# Pg2-Filter_and_Gain.net
KiCad netlist of a schematic drawn in Altium Designer
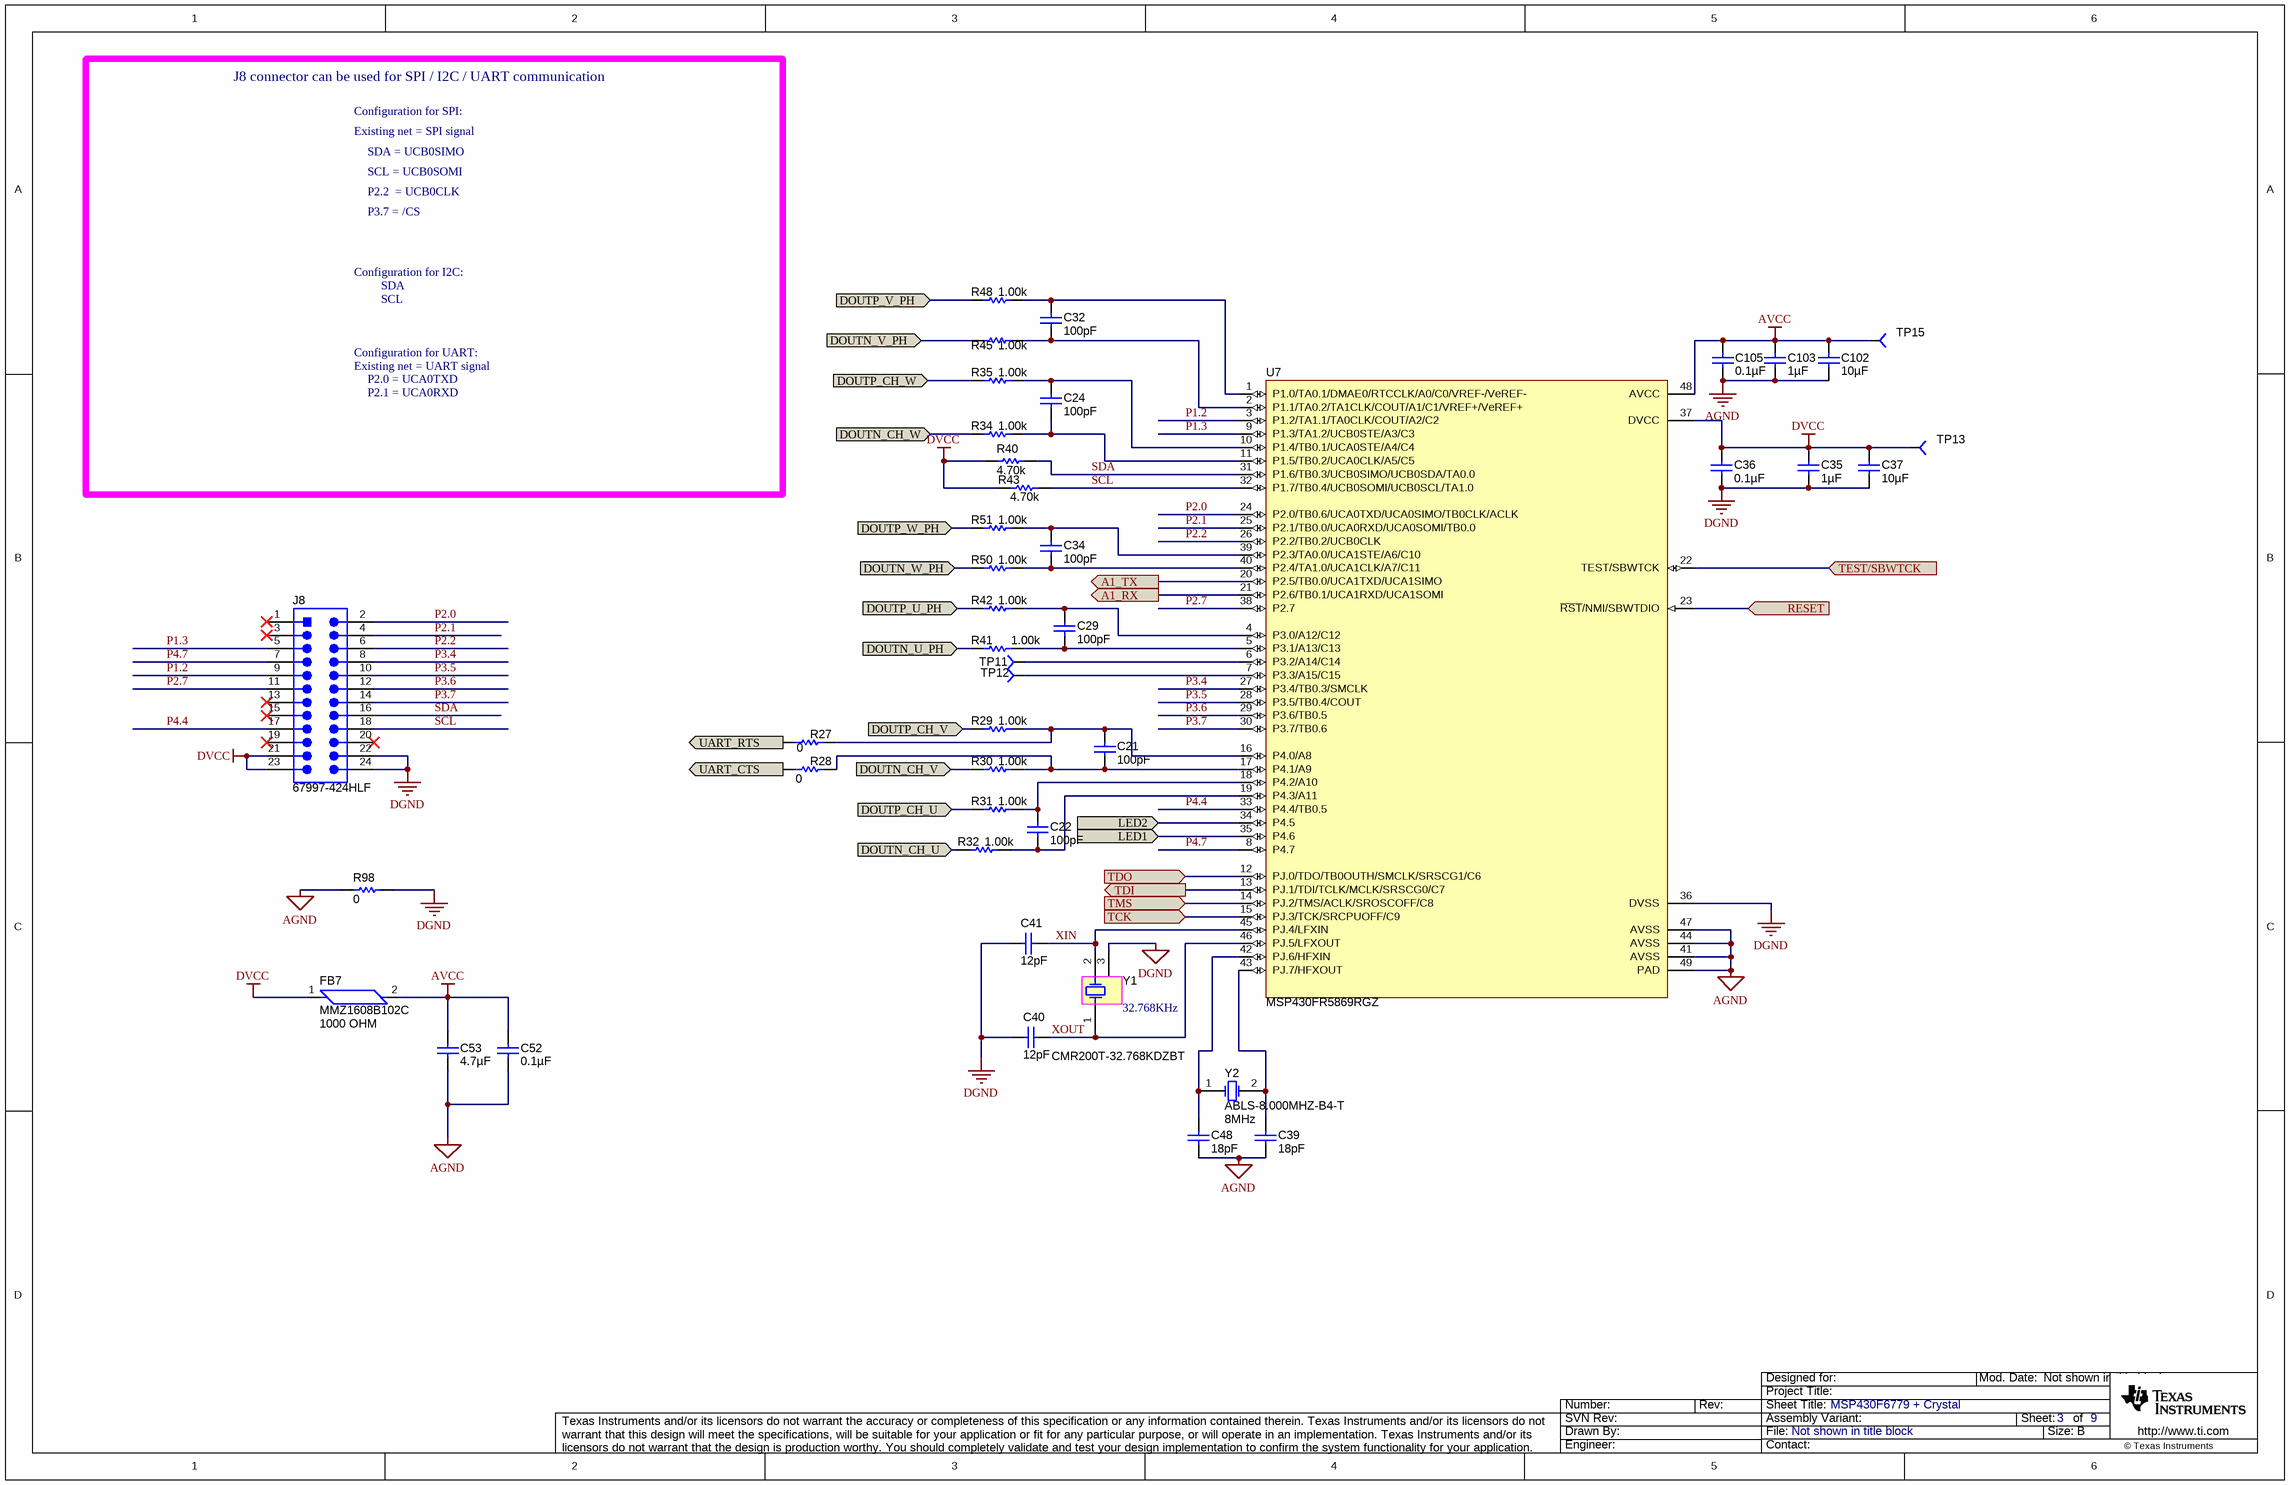
[diagram p0: Pg2-Filter and Gain.SchDoc]

(export (version "E")
  (design (tool "Eeschema 10.0.6"))
  (components
    (comp (ref "C21")
      (value "C0603C101J5GAC")
      (footprint "0603")
      (description "CAP, CERM, 100 pF, 50 V, +/- 5%, C0G/NP0, 0603")
      (fields
        (field (name "VALUEDISPLAYED") "100pF")
        (field (name "MANUFACTURER") "Kemet")
        (field (name "PUBLISHER") "Texas Instruments")
      )
      (libsource (lib "Capacitor_Ceramic") (part "C0603C101J5GAC"))
    )
    (comp (ref "C22")
      (value "C0603C101J5GAC")
      (footprint "0603")
      (description "CAP, CERM, 100 pF, 50 V, +/- 5%, C0G/NP0, 0603")
      (fields
        (field (name "VALUEDISPLAYED") "100pF")
        (field (name "MANUFACTURER") "Kemet")
        (field (name "PUBLISHER") "Texas Instruments")
      )
      (libsource (lib "Capacitor_Ceramic") (part "C0603C101J5GAC"))
    )
    (comp (ref "C24")
      (value "C0603C101J5GAC")
      (footprint "0603")
      (description "CAP, CERM, 100 pF, 50 V, +/- 5%, C0G/NP0, 0603")
      (fields
        (field (name "VALUEDISPLAYED") "100pF")
        (field (name "MANUFACTURER") "Kemet")
        (field (name "PUBLISHER") "Texas Instruments")
      )
      (libsource (lib "Capacitor_Ceramic") (part "C0603C101J5GAC"))
    )
    (comp (ref "C29")
      (value "C0603C101J5GAC")
      (footprint "0603")
      (description "CAP, CERM, 100 pF, 50 V, +/- 5%, C0G/NP0, 0603")
      (fields
        (field (name "VALUEDISPLAYED") "100pF")
        (field (name "MANUFACTURER") "Kemet")
        (field (name "PUBLISHER") "Texas Instruments")
      )
      (libsource (lib "Capacitor_Ceramic") (part "C0603C101J5GAC"))
    )
    (comp (ref "C32")
      (value "C0603C101J5GAC")
      (footprint "0603")
      (description "CAP, CERM, 100 pF, 50 V, +/- 5%, C0G/NP0, 0603")
      (fields
        (field (name "VALUEDISPLAYED") "100pF")
        (field (name "MANUFACTURER") "Kemet")
        (field (name "PUBLISHER") "Texas Instruments")
      )
      (libsource (lib "Capacitor_Ceramic") (part "C0603C101J5GAC"))
    )
    (comp (ref "C34")
      (value "C0603C101J5GAC")
      (footprint "0603")
      (description "CAP, CERM, 100 pF, 50 V, +/- 5%, C0G/NP0, 0603")
      (fields
        (field (name "VALUEDISPLAYED") "100pF")
        (field (name "MANUFACTURER") "Kemet")
        (field (name "PUBLISHER") "Texas Instruments")
      )
      (libsource (lib "Capacitor_Ceramic") (part "C0603C101J5GAC"))
    )
    (comp (ref "C35")
      (value "GRM188R71C105KA12D")
      (footprint "0603")
      (description "CAP, CERM, 1 µF, 16 V, +/- 10%, X7R, 0603")
      (fields
        (field (name "VALUEDISPLAYED") "1µF")
        (field (name "MANUFACTURER") "MuRata")
        (field (name "PUBLISHER") "Texas Instruments")
      )
      (libsource (lib "Capacitor_Ceramic") (part "GRM188R71C105KA12D"))
    )
    (comp (ref "C36")
      (value "0603YC104JAT2A")
      (footprint "0603")
      (description "CAP, CERM, 0.1 µF, 16 V, +/- 5%, X7R, 0603")
      (fields
        (field (name "VALUEDISPLAYED") "0.1µF")
        (field (name "MANUFACTURER") "AVX")
        (field (name "PUBLISHER") "Texas Instruments")
      )
      (libsource (lib "Capacitor_Ceramic") (part "0603YC104JAT2A"))
    )
    (comp (ref "C37")
      (value "GRM188R61E106MA73")
      (footprint "0603")
      (description "CAP, CERM, 10uF, 25V, +/-20%, X5R, 0603")
      (fields
        (field (name "VALUEDISPLAYED") "10µF")
        (field (name "MANUFACTURER") "MuRata")
        (field (name "PUBLISHER") "Texas Instruments")
      )
      (libsource (lib "Capacitor_Ceramic") (part "GRM188R61E106MA73"))
    )
    (comp (ref "C39")
      (value "GRM1885C1H180JA01D")
      (footprint "0603")
      (description "CAP, CERM, 18pF, 50V, +/-5%, C0G/NP0, 0603")
      (fields
        (field (name "VALUEDISPLAYED") "18pF")
        (field (name "MANUFACTURER") "MuRata")
        (field (name "PUBLISHER") "Texas Instruments")
      )
      (libsource (lib "Capacitor_Ceramic") (part "GRM1885C1H180JA01D"))
    )
    (comp (ref "C40")
      (value "06035A120JAT2A")
      (footprint "0603")
      (description "CAP, CERM, 12pF, 50V, +/-5%, C0G/NP0, 0603")
      (fields
        (field (name "VALUEDISPLAYED") "12pF")
        (field (name "MANUFACTURER") "AVX")
        (field (name "PUBLISHER") "Texas Instruments")
      )
      (libsource (lib "Capacitor_Ceramic") (part "06035A120JAT2A"))
    )
    (comp (ref "C41")
      (value "06035A120JAT2A")
      (footprint "0603")
      (description "CAP, CERM, 12pF, 50V, +/-5%, C0G/NP0, 0603")
      (fields
        (field (name "VALUEDISPLAYED") "12pF")
        (field (name "MANUFACTURER") "AVX")
        (field (name "PUBLISHER") "Texas Instruments")
      )
      (libsource (lib "Capacitor_Ceramic") (part "06035A120JAT2A"))
    )
    (comp (ref "C48")
      (value "GRM1885C1H180JA01D")
      (footprint "0603")
      (description "CAP, CERM, 18pF, 50V, +/-5%, C0G/NP0, 0603")
      (fields
        (field (name "VALUEDISPLAYED") "18pF")
        (field (name "MANUFACTURER") "MuRata")
        (field (name "PUBLISHER") "Texas Instruments")
      )
      (libsource (lib "Capacitor_Ceramic") (part "GRM1885C1H180JA01D"))
    )
    (comp (ref "C52")
      (value "06033C104JAT2A")
      (footprint "0603")
      (description "CAP, CERM, 0.1uF, 25V, +/-5%, X7R, 0603")
      (fields
        (field (name "VALUEDISPLAYED") "0.1µF")
        (field (name "MANUFACTURER") "AVX")
        (field (name "PUBLISHER") "Texas Instruments")
      )
      (libsource (lib "Capacitor_Ceramic") (part "06033C104JAT2A"))
    )
    (comp (ref "C53")
      (value "0603ZD475KAT2A")
      (footprint "0603")
      (description "CAP, CERM, 4.7uF, 10V, +/-10%, X5R, 0603")
      (fields
        (field (name "VALUEDISPLAYED") "4.7µF")
        (field (name "MANUFACTURER") "AVX")
        (field (name "PUBLISHER") "Texas Instruments")
      )
      (libsource (lib "Capacitor_Ceramic") (part "0603ZD475KAT2A"))
    )
    (comp (ref "C102")
      (value "GRM188R61E106MA73")
      (footprint "0603")
      (description "CAP, CERM, 10uF, 25V, +/-20%, X5R, 0603")
      (fields
        (field (name "VALUEDISPLAYED") "10µF")
        (field (name "MANUFACTURER") "MuRata")
        (field (name "PUBLISHER") "Texas Instruments")
      )
      (libsource (lib "Capacitor_Ceramic") (part "GRM188R61E106MA73"))
    )
    (comp (ref "C103")
      (value "GRM188R71C105KA12D")
      (footprint "0603")
      (description "CAP, CERM, 1 µF, 16 V, +/- 10%, X7R, 0603")
      (fields
        (field (name "VALUEDISPLAYED") "1µF")
        (field (name "MANUFACTURER") "MuRata")
        (field (name "PUBLISHER") "Texas Instruments")
      )
      (libsource (lib "Capacitor_Ceramic") (part "GRM188R71C105KA12D"))
    )
    (comp (ref "C105")
      (value "0603YC104JAT2A")
      (footprint "0603")
      (description "CAP, CERM, 0.1 µF, 16 V, +/- 5%, X7R, 0603")
      (fields
        (field (name "VALUEDISPLAYED") "0.1µF")
        (field (name "MANUFACTURER") "AVX")
        (field (name "PUBLISHER") "Texas Instruments")
      )
      (libsource (lib "Capacitor_Ceramic") (part "0603YC104JAT2A"))
    )
    (comp (ref "FB7")
      (value "MMZ1608B102C")
      (footprint "FB0603")
      (description "FERRITE CHIP 1000 OHM 300MA 0603")
      (fields
        (field (name "MANUFACTURER") "TDK Corporation")
        (field (name "ALTIUM_VALUE") "1000 OHM")
        (field (name "PUBLISHER") "TI")
      )
      (libsource (lib "Isolated current sensing") (part "MMZ1608B102C"))
    )
    (comp (ref "J8")
      (value "67997-424HLF")
      (footprint "TSW-112-07-G-D")
      (description "Header, TH, 100mil, 12x2, Gold plated, 230 mil above insulator")
      (fields
        (field (name "MANUFACTURER") "FCI")
        (field (name "SYMBOLCREATOR") "a0412235")
        (field (name "PUBLISHER") "Texas Instruments")
      )
      (libsource (lib "Connectors") (part "TSW-112-07-G-D"))
    )
    (comp (ref "R27")
      (value "0")
      (footprint "0603")
      (description "RES, 0 ohm, 5%, 0.1W, 0603")
      (fields
        (field (name "PARTNUMBER") "CRCW06030000Z0EA")
        (field (name "MANUFACTURER") "Vishay-Dale")
        (field (name "PUBLISHER") "Texas Instruments")
      )
      (libsource (lib "Resistor_0603") (part "CRCW06030000Z0EA"))
    )
    (comp (ref "R28")
      (value "0")
      (footprint "0603")
      (description "RES, 0 ohm, 5%, 0.1W, 0603")
      (fields
        (field (name "PARTNUMBER") "CRCW06030000Z0EA")
        (field (name "MANUFACTURER") "Vishay-Dale")
        (field (name "PUBLISHER") "Texas Instruments")
      )
      (libsource (lib "Resistor_0603") (part "CRCW06030000Z0EA"))
    )
    (comp (ref "R29")
      (value "RG1608P-102-B-T5")
      (footprint "0603")
      (description "RES, 1.00 k, 0.1%, 0.1 W, 0603")
      (fields
        (field (name "VALUEDISPLAYED") "1.00k")
        (field (name "MANUFACTURER") "Susumu Co Ltd")
        (field (name "PUBLISHER") "Texas Instruments")
      )
      (libsource (lib "Resistor_0603") (part "RG1608P-102-B-T5"))
    )
    (comp (ref "R30")
      (value "RG1608P-102-B-T5")
      (footprint "0603")
      (description "RES, 1.00 k, 0.1%, 0.1 W, 0603")
      (fields
        (field (name "VALUEDISPLAYED") "1.00k")
        (field (name "MANUFACTURER") "Susumu Co Ltd")
        (field (name "PUBLISHER") "Texas Instruments")
      )
      (libsource (lib "Resistor_0603") (part "RG1608P-102-B-T5"))
    )
    (comp (ref "R31")
      (value "RG1608P-102-B-T5")
      (footprint "0603")
      (description "RES, 1.00 k, 0.1%, 0.1 W, 0603")
      (fields
        (field (name "VALUEDISPLAYED") "1.00k")
        (field (name "MANUFACTURER") "Susumu Co Ltd")
        (field (name "PUBLISHER") "Texas Instruments")
      )
      (libsource (lib "Resistor_0603") (part "RG1608P-102-B-T5"))
    )
    (comp (ref "R32")
      (value "RG1608P-102-B-T5")
      (footprint "0603")
      (description "RES, 1.00 k, 0.1%, 0.1 W, 0603")
      (fields
        (field (name "VALUEDISPLAYED") "1.00k")
        (field (name "MANUFACTURER") "Susumu Co Ltd")
        (field (name "PUBLISHER") "Texas Instruments")
      )
      (libsource (lib "Resistor_0603") (part "RG1608P-102-B-T5"))
    )
    (comp (ref "R34")
      (value "RG1608P-102-B-T5")
      (footprint "0603")
      (description "RES, 1.00 k, 0.1%, 0.1 W, 0603")
      (fields
        (field (name "VALUEDISPLAYED") "1.00k")
        (field (name "MANUFACTURER") "Susumu Co Ltd")
        (field (name "PUBLISHER") "Texas Instruments")
      )
      (libsource (lib "Resistor_0603") (part "RG1608P-102-B-T5"))
    )
    (comp (ref "R35")
      (value "RG1608P-102-B-T5")
      (footprint "0603")
      (description "RES, 1.00 k, 0.1%, 0.1 W, 0603")
      (fields
        (field (name "VALUEDISPLAYED") "1.00k")
        (field (name "MANUFACTURER") "Susumu Co Ltd")
        (field (name "PUBLISHER") "Texas Instruments")
      )
      (libsource (lib "Resistor_0603") (part "RG1608P-102-B-T5"))
    )
    (comp (ref "R40")
      (value "4.70k")
      (footprint "0603")
      (description "RES, 4.70k ohm, 1%, 0.1W, 0603")
      (fields
        (field (name "PARTNUMBER") "RC0603FR-074K7L")
        (field (name "MANUFACTURER") "Yageo America")
        (field (name "PUBLISHER") "Texas Instruments")
      )
      (libsource (lib "Resistor_0603") (part "RC0603FR-074K7L"))
    )
    (comp (ref "R41")
      (value "RG1608P-102-B-T5")
      (footprint "0603")
      (description "RES, 1.00 k, 0.1%, 0.1 W, 0603")
      (fields
        (field (name "VALUEDISPLAYED") "1.00k")
        (field (name "MANUFACTURER") "Susumu Co Ltd")
        (field (name "PUBLISHER") "Texas Instruments")
      )
      (libsource (lib "Resistor_0603") (part "RG1608P-102-B-T5"))
    )
    (comp (ref "R42")
      (value "RG1608P-102-B-T5")
      (footprint "0603")
      (description "RES, 1.00 k, 0.1%, 0.1 W, 0603")
      (fields
        (field (name "VALUEDISPLAYED") "1.00k")
        (field (name "MANUFACTURER") "Susumu Co Ltd")
        (field (name "PUBLISHER") "Texas Instruments")
      )
      (libsource (lib "Resistor_0603") (part "RG1608P-102-B-T5"))
    )
    (comp (ref "R43")
      (value "4.70k")
      (footprint "0603")
      (description "RES, 4.70k ohm, 1%, 0.1W, 0603")
      (fields
        (field (name "PARTNUMBER") "RC0603FR-074K7L")
        (field (name "MANUFACTURER") "Yageo America")
        (field (name "PUBLISHER") "Texas Instruments")
      )
      (libsource (lib "Resistor_0603") (part "RC0603FR-074K7L"))
    )
    (comp (ref "R45")
      (value "RG1608P-102-B-T5")
      (footprint "0603")
      (description "RES, 1.00 k, 0.1%, 0.1 W, 0603")
      (fields
        (field (name "VALUEDISPLAYED") "1.00k")
        (field (name "MANUFACTURER") "Susumu Co Ltd")
        (field (name "PUBLISHER") "Texas Instruments")
      )
      (libsource (lib "Resistor_0603") (part "RG1608P-102-B-T5"))
    )
    (comp (ref "R48")
      (value "RG1608P-102-B-T5")
      (footprint "0603")
      (description "RES, 1.00 k, 0.1%, 0.1 W, 0603")
      (fields
        (field (name "VALUEDISPLAYED") "1.00k")
        (field (name "MANUFACTURER") "Susumu Co Ltd")
        (field (name "PUBLISHER") "Texas Instruments")
      )
      (libsource (lib "Resistor_0603") (part "RG1608P-102-B-T5"))
    )
    (comp (ref "R50")
      (value "RG1608P-102-B-T5")
      (footprint "0603")
      (description "RES, 1.00 k, 0.1%, 0.1 W, 0603")
      (fields
        (field (name "VALUEDISPLAYED") "1.00k")
        (field (name "MANUFACTURER") "Susumu Co Ltd")
        (field (name "PUBLISHER") "Texas Instruments")
      )
      (libsource (lib "Resistor_0603") (part "RG1608P-102-B-T5"))
    )
    (comp (ref "R51")
      (value "RG1608P-102-B-T5")
      (footprint "0603")
      (description "RES, 1.00 k, 0.1%, 0.1 W, 0603")
      (fields
        (field (name "VALUEDISPLAYED") "1.00k")
        (field (name "MANUFACTURER") "Susumu Co Ltd")
        (field (name "PUBLISHER") "Texas Instruments")
      )
      (libsource (lib "Resistor_0603") (part "RG1608P-102-B-T5"))
    )
    (comp (ref "R98")
      (value "0")
      (footprint "0805_HV")
      (description "RES, 0 ohm, 5%, 0.125W, 0805")
      (fields
        (field (name "PARTNUMBER") "CRCW08050000Z0EA")
        (field (name "MANUFACTURER") "Vishay-Dale")
        (field (name "PUBLISHER") "Texas Instruments")
      )
      (libsource (lib "Resistor_0805") (part "CRCW0805330KJNEA"))
    )
    (comp (ref "TP11")
      (value "TP-040_RND")
      (footprint "TP-040_RND")
      (description "Test Point, O.040 Hole")
      (fields (field (name "MANUFACTURER") "STD"))
      (libsource (lib "PADSlegacy_Hardware") (part "TP-040_RND"))
    )
    (comp (ref "TP12")
      (value "TP-040_RND")
      (footprint "TP-040_RND")
      (description "Test Point, O.040 Hole")
      (fields (field (name "MANUFACTURER") "STD"))
      (libsource (lib "PADSlegacy_Hardware") (part "TP-040_RND"))
    )
    (comp (ref "TP13")
      (value "TP-040_RND")
      (footprint "TP-040_RND")
      (description "Test Point, O.040 Hole")
      (fields (field (name "MANUFACTURER") "STD"))
      (libsource (lib "PADSlegacy_Hardware") (part "TP-040_RND"))
    )
    (comp (ref "TP15")
      (value "TP-040_RND")
      (footprint "TP-040_RND")
      (description "Test Point, O.040 Hole")
      (fields (field (name "MANUFACTURER") "STD"))
      (libsource (lib "PADSlegacy_Hardware") (part "TP-040_RND"))
    )
    (comp (ref "U7")
      (value "MSP430FR5869RGZ")
      (footprint "RGZ0048B")
      (description "Mixed Signal Microcontroller, RGZ0048B")
      (fields
        (field (name "MANUFACTURER") "Texas Instruments")
        (field (name "SYMBOLCREATOR") "a0411947")
        (field (name "PUBLISHER") "Texas Instruments")
      )
      (libsource (lib "TI_Pre_Release") (part "MSP430FR5969IRGZ"))
    )
    (comp (ref "Y1")
      (value "CMR200T-32.768KDZBT")
      (footprint "XTAL_CMR200T")
      (description "CRYSTAL, 32.768KHz, 6PF, +/- 20PPM, SMD-3P")
      (fields
        (field (name "MANUFACTURER") "CITIZEN")
        (field (name "FREQUENCY") "32.768KHz")
        (field (name "SYMBOLCREATOR") "x0199378")
      )
      (libsource (lib "SYMBOLS") (part "CMR200T-32.768KDZBT"))
    )
    (comp (ref "Y2")
      (value "ABLS-8.000MHZ-B4-T")
      (footprint "XTAL_CSM-7X")
      (description "Crystal, 8MHz, 18pF, SMD")
      (fields
        (field (name "FREQUENCY") "8MHz")
        (field (name "MANUFACTURER") "Abracon Corportation")
        (field (name "SYMBOLCREATOR") "a0412235")
        (field (name "PUBLISHER") "Texas Instruments")
      )
      (libsource (lib "Oscillators") (part "ABLS-8.000MHZ-B4-T"))
    )
  )
  (nets
    (net (code "1") (name "/A1_RX") (class "Default")
      (node (ref "U7") (pin "21") (pinfunction "P2.6/TB0.1/UCA1RXD/UCA1SOMI_21") (pintype "bidirectional"))
    )
    (net (code "2") (name "/A1_TX") (class "Default")
      (node (ref "U7") (pin "20") (pinfunction "P2.5/TB0.0/UCA1TXD/UCA1SIMO_20") (pintype "bidirectional"))
    )
    (net (code "3") (name "/DOUTN_CH_U") (class "Default")
      (node (ref "R32") (pin "1") (pinfunction "1_1") (pintype "passive"))
    )
    (net (code "4") (name "/DOUTN_CH_V") (class "Default")
      (node (ref "R30") (pin "1") (pinfunction "1_1") (pintype "passive"))
    )
    (net (code "5") (name "/DOUTN_CH_W") (class "Default")
      (node (ref "R34") (pin "1") (pinfunction "1_1") (pintype "passive"))
    )
    (net (code "6") (name "/DOUTN_U_PH") (class "Default")
      (node (ref "R41") (pin "1") (pinfunction "1_1") (pintype "passive"))
    )
    (net (code "7") (name "/DOUTN_V_PH") (class "Default")
      (node (ref "R45") (pin "1") (pinfunction "1_1") (pintype "passive"))
    )
    (net (code "8") (name "/DOUTN_W_PH") (class "Default")
      (node (ref "R50") (pin "1") (pinfunction "1_1") (pintype "passive"))
    )
    (net (code "9") (name "/DOUTP_CH_U") (class "Default")
      (node (ref "R31") (pin "1") (pinfunction "1_1") (pintype "passive"))
    )
    (net (code "10") (name "/DOUTP_CH_V") (class "Default")
      (node (ref "R29") (pin "1") (pinfunction "1_1") (pintype "passive"))
    )
    (net (code "11") (name "/DOUTP_CH_W") (class "Default")
      (node (ref "R35") (pin "1") (pinfunction "1_1") (pintype "passive"))
    )
    (net (code "12") (name "/DOUTP_U_PH") (class "Default")
      (node (ref "R42") (pin "1") (pinfunction "1_1") (pintype "passive"))
    )
    (net (code "13") (name "/DOUTP_V_PH") (class "Default")
      (node (ref "R48") (pin "1") (pinfunction "1_1") (pintype "passive"))
    )
    (net (code "14") (name "/DOUTP_W_PH") (class "Default")
      (node (ref "R51") (pin "1") (pinfunction "1_1") (pintype "passive"))
    )
    (net (code "15") (name "/LED1") (class "Default")
      (node (ref "U7") (pin "35") (pinfunction "P4.6_35") (pintype "bidirectional"))
    )
    (net (code "16") (name "/LED2") (class "Default")
      (node (ref "U7") (pin "34") (pinfunction "P4.5_34") (pintype "bidirectional"))
    )
    (net (code "17") (name "/P1.2") (class "Default")
      (node (ref "J8") (pin "9") (pinfunction "9_9") (pintype "passive"))
      (node (ref "U7") (pin "3") (pinfunction "P1.2/TA1.1/TA0CLK/COUT/A2/C2_3") (pintype "bidirectional"))
    )
    (net (code "18") (name "/P1.3") (class "Default")
      (node (ref "J8") (pin "5") (pinfunction "5_5") (pintype "passive"))
      (node (ref "U7") (pin "9") (pinfunction "P1.3/TA1.2/UCB0STE/A3/C3_9") (pintype "bidirectional"))
    )
    (net (code "19") (name "/P2.0") (class "Default")
      (node (ref "J8") (pin "2") (pinfunction "2_2") (pintype "passive"))
      (node (ref "U7") (pin "24") (pinfunction "P2.0/TB0.6/UCA0TXD/UCA0SIMO/TB0CLK/ACLK_24") (pintype "bidirectional"))
    )
    (net (code "20") (name "/P2.1") (class "Default")
      (node (ref "J8") (pin "4") (pinfunction "4_4") (pintype "passive"))
      (node (ref "U7") (pin "25") (pinfunction "P2.1/TB0.0/UCA0RXD/UCA0SOMI/TB0.0_25") (pintype "bidirectional"))
    )
    (net (code "21") (name "/P2.2") (class "Default")
      (node (ref "J8") (pin "6") (pinfunction "6_6") (pintype "passive"))
      (node (ref "U7") (pin "26") (pinfunction "P2.2/TB0.2/UCB0CLK_26") (pintype "bidirectional"))
    )
    (net (code "22") (name "/P2.7") (class "Default")
      (node (ref "J8") (pin "11") (pinfunction "11_11") (pintype "passive"))
      (node (ref "U7") (pin "38") (pinfunction "P2.7_38") (pintype "bidirectional"))
    )
    (net (code "23") (name "/P3.4") (class "Default")
      (node (ref "J8") (pin "8") (pinfunction "8_8") (pintype "passive"))
      (node (ref "U7") (pin "27") (pinfunction "P3.4/TB0.3/SMCLK_27") (pintype "bidirectional"))
    )
    (net (code "24") (name "/P3.5") (class "Default")
      (node (ref "J8") (pin "10") (pinfunction "10_10") (pintype "passive"))
      (node (ref "U7") (pin "28") (pinfunction "P3.5/TB0.4/COUT_28") (pintype "bidirectional"))
    )
    (net (code "25") (name "/P3.6") (class "Default")
      (node (ref "J8") (pin "12") (pinfunction "12_12") (pintype "passive"))
      (node (ref "U7") (pin "29") (pinfunction "P3.6/TB0.5_29") (pintype "bidirectional"))
    )
    (net (code "26") (name "/P3.7") (class "Default")
      (node (ref "J8") (pin "14") (pinfunction "14_14") (pintype "passive"))
      (node (ref "U7") (pin "30") (pinfunction "P3.7/TB0.6_30") (pintype "bidirectional"))
    )
    (net (code "27") (name "/P4.4") (class "Default")
      (node (ref "J8") (pin "17") (pinfunction "17_17") (pintype "passive"))
      (node (ref "U7") (pin "33") (pinfunction "P4.4/TB0.5_33") (pintype "bidirectional"))
    )
    (net (code "28") (name "/P4.7") (class "Default")
      (node (ref "J8") (pin "7") (pinfunction "7_7") (pintype "passive"))
      (node (ref "U7") (pin "8") (pinfunction "P4.7_8") (pintype "bidirectional"))
    )
    (net (code "29") (name "/RESET") (class "Default")
      (node (ref "U7") (pin "23") (pinfunction "~{RST}/NMI/SBWTDIO_23") (pintype "input"))
    )
    (net (code "30") (name "/SCL") (class "Default")
      (node (ref "J8") (pin "18") (pinfunction "18_18") (pintype "passive"))
      (node (ref "R43") (pin "2") (pinfunction "2_2") (pintype "passive"))
      (node (ref "U7") (pin "32") (pinfunction "P1.7/TB0.4/UCB0SOMI/UCB0SCL/TA1.0_32") (pintype "bidirectional"))
    )
    (net (code "31") (name "/SDA") (class "Default")
      (node (ref "J8") (pin "16") (pinfunction "16_16") (pintype "passive"))
      (node (ref "R40") (pin "2") (pinfunction "2_2") (pintype "passive"))
      (node (ref "U7") (pin "31") (pinfunction "P1.6/TB0.3/UCB0SIMO/UCB0SDA/TA0.0_31") (pintype "bidirectional"))
    )
    (net (code "32") (name "/TCK") (class "Default")
      (node (ref "U7") (pin "15") (pinfunction "PJ.3/TCK/SRCPUOFF/C9_15") (pintype "bidirectional"))
    )
    (net (code "33") (name "/TDI") (class "Default")
      (node (ref "U7") (pin "13") (pinfunction "PJ.1/TDI/TCLK/MCLK/SRSCG0/C7_13") (pintype "bidirectional"))
    )
    (net (code "34") (name "/TDO") (class "Default")
      (node (ref "U7") (pin "12") (pinfunction "PJ.0/TDO/TB0OUTH/SMCLK/SRSCG1/C6_12") (pintype "bidirectional"))
    )
    (net (code "35") (name "/TEST{slash}SBWTCK") (class "Default")
      (node (ref "U7") (pin "22") (pinfunction "TEST/SBWTCK_22") (pintype "bidirectional"))
    )
    (net (code "36") (name "/TMS") (class "Default")
      (node (ref "U7") (pin "14") (pinfunction "PJ.2/TMS/ACLK/SROSCOFF/C8_14") (pintype "bidirectional"))
    )
    (net (code "37") (name "/UART_CTS") (class "Default")
      (node (ref "R28") (pin "1") (pinfunction "1_1") (pintype "passive"))
    )
    (net (code "38") (name "/UART_RTS") (class "Default")
      (node (ref "R27") (pin "1") (pinfunction "1_1") (pintype "passive"))
    )
    (net (code "39") (name "/XIN") (class "Default")
      (node (ref "C41") (pin "1") (pinfunction "1_1") (pintype "passive"))
      (node (ref "U7") (pin "45") (pinfunction "PJ.4/LFXIN_45") (pintype "bidirectional"))
      (node (ref "Y1") (pin "2") (pinfunction "2_2") (pintype "passive"))
    )
    (net (code "40") (name "/XOUT") (class "Default")
      (node (ref "C40") (pin "1") (pinfunction "1_1") (pintype "passive"))
      (node (ref "U7") (pin "46") (pinfunction "PJ.5/LFXOUT_46") (pintype "bidirectional"))
      (node (ref "Y1") (pin "1") (pinfunction "1_1") (pintype "passive"))
    )
    (net (code "41") (name "AGND") (class "Default")
      (node (ref "C102") (pin "2") (pinfunction "2_2") (pintype "passive"))
      (node (ref "C103") (pin "2") (pinfunction "2_2") (pintype "passive"))
      (node (ref "C105") (pin "2") (pinfunction "2_2") (pintype "passive"))
      (node (ref "C39") (pin "2") (pinfunction "2_2") (pintype "passive"))
      (node (ref "C48") (pin "2") (pinfunction "2_2") (pintype "passive"))
      (node (ref "C52") (pin "2") (pinfunction "2_2") (pintype "passive"))
      (node (ref "C53") (pin "2") (pinfunction "2_2") (pintype "passive"))
      (node (ref "R98") (pin "1") (pinfunction "1_1") (pintype "passive"))
      (node (ref "U7") (pin "41") (pinfunction "AVSS_41") (pintype "power_in"))
      (node (ref "U7") (pin "44") (pinfunction "AVSS_44") (pintype "power_in"))
      (node (ref "U7") (pin "47") (pinfunction "AVSS_47") (pintype "power_in"))
      (node (ref "U7") (pin "49") (pinfunction "PAD_49") (pintype "passive"))
    )
    (net (code "42") (name "AVCC") (class "Default")
      (node (ref "C102") (pin "1") (pinfunction "1_1") (pintype "passive"))
      (node (ref "C103") (pin "1") (pinfunction "1_1") (pintype "passive"))
      (node (ref "C105") (pin "1") (pinfunction "1_1") (pintype "passive"))
      (node (ref "C52") (pin "1") (pinfunction "1_1") (pintype "passive"))
      (node (ref "C53") (pin "1") (pinfunction "1_1") (pintype "passive"))
      (node (ref "FB7") (pin "2") (pinfunction "2_2") (pintype "passive"))
      (node (ref "TP15") (pin "1") (pinfunction "1_1") (pintype "passive"))
      (node (ref "U7") (pin "48") (pinfunction "AVCC_48") (pintype "power_in"))
    )
    (net (code "43") (name "DGND") (class "Default")
      (node (ref "C35") (pin "2") (pinfunction "2_2") (pintype "passive"))
      (node (ref "C36") (pin "2") (pinfunction "2_2") (pintype "passive"))
      (node (ref "C37") (pin "2") (pinfunction "2_2") (pintype "passive"))
      (node (ref "C40") (pin "2") (pinfunction "2_2") (pintype "passive"))
      (node (ref "C41") (pin "2") (pinfunction "2_2") (pintype "passive"))
      (node (ref "J8") (pin "22") (pinfunction "22_22") (pintype "passive"))
      (node (ref "J8") (pin "24") (pinfunction "24_24") (pintype "passive"))
      (node (ref "R98") (pin "2") (pinfunction "2_2") (pintype "passive"))
      (node (ref "U7") (pin "36") (pinfunction "DVSS_36") (pintype "power_in"))
      (node (ref "Y1") (pin "3") (pinfunction "3_3") (pintype "passive"))
    )
    (net (code "44") (name "DVCC") (class "Default")
      (node (ref "C35") (pin "1") (pinfunction "1_1") (pintype "passive"))
      (node (ref "C36") (pin "1") (pinfunction "1_1") (pintype "passive"))
      (node (ref "C37") (pin "1") (pinfunction "1_1") (pintype "passive"))
      (node (ref "FB7") (pin "1") (pinfunction "1_1") (pintype "passive"))
      (node (ref "J8") (pin "21") (pinfunction "21_21") (pintype "passive"))
      (node (ref "J8") (pin "23") (pinfunction "23_23") (pintype "passive"))
      (node (ref "R40") (pin "1") (pinfunction "1_1") (pintype "passive"))
      (node (ref "R43") (pin "1") (pinfunction "1_1") (pintype "passive"))
      (node (ref "TP13") (pin "1") (pinfunction "1_1") (pintype "passive"))
      (node (ref "U7") (pin "37") (pinfunction "DVCC_37") (pintype "power_in"))
    )
    (net (code "45") (name "Net-(U7-P1.0{slash}TA0.1{slash}DMAE0{slash}RTCCLK{slash}A0{slash}C0{slash}VREF-{slash}VeREF-)") (class "Default")
      (node (ref "C32") (pin "2") (pinfunction "2_2") (pintype "passive"))
      (node (ref "R48") (pin "2") (pinfunction "2_2") (pintype "passive"))
      (node (ref "U7") (pin "1") (pinfunction "P1.0/TA0.1/DMAE0/RTCCLK/A0/C0/VREF-/VeREF-_1") (pintype "bidirectional"))
    )
    (net (code "46") (name "Net-(U7-P1.1{slash}TA0.2{slash}TA1CLK{slash}COUT{slash}A1{slash}C1{slash}VREF+{slash}VeREF+)") (class "Default")
      (node (ref "C32") (pin "1") (pinfunction "1_1") (pintype "passive"))
      (node (ref "R45") (pin "2") (pinfunction "2_2") (pintype "passive"))
      (node (ref "U7") (pin "2") (pinfunction "P1.1/TA0.2/TA1CLK/COUT/A1/C1/VREF+/VeREF+_2") (pintype "bidirectional"))
    )
    (net (code "47") (name "Net-(U7-P1.4{slash}TB0.1{slash}UCA0STE{slash}A4{slash}C4)") (class "Default")
      (node (ref "C24") (pin "2") (pinfunction "2_2") (pintype "passive"))
      (node (ref "R35") (pin "2") (pinfunction "2_2") (pintype "passive"))
      (node (ref "U7") (pin "10") (pinfunction "P1.4/TB0.1/UCA0STE/A4/C4_10") (pintype "bidirectional"))
    )
    (net (code "48") (name "Net-(U7-P1.5{slash}TB0.2{slash}UCA0CLK{slash}A5{slash}C5)") (class "Default")
      (node (ref "C24") (pin "1") (pinfunction "1_1") (pintype "passive"))
      (node (ref "R34") (pin "2") (pinfunction "2_2") (pintype "passive"))
      (node (ref "U7") (pin "11") (pinfunction "P1.5/TB0.2/UCA0CLK/A5/C5_11") (pintype "bidirectional"))
    )
    (net (code "49") (name "Net-(U7-P2.3{slash}TA0.0{slash}UCA1STE{slash}A6{slash}C10)") (class "Default")
      (node (ref "C34") (pin "2") (pinfunction "2_2") (pintype "passive"))
      (node (ref "R51") (pin "2") (pinfunction "2_2") (pintype "passive"))
      (node (ref "U7") (pin "39") (pinfunction "P2.3/TA0.0/UCA1STE/A6/C10_39") (pintype "bidirectional"))
    )
    (net (code "50") (name "Net-(U7-P2.4{slash}TA1.0{slash}UCA1CLK{slash}A7{slash}C11)") (class "Default")
      (node (ref "C34") (pin "1") (pinfunction "1_1") (pintype "passive"))
      (node (ref "R50") (pin "2") (pinfunction "2_2") (pintype "passive"))
      (node (ref "U7") (pin "40") (pinfunction "P2.4/TA1.0/UCA1CLK/A7/C11_40") (pintype "bidirectional"))
    )
    (net (code "51") (name "Net-(U7-P3.0{slash}A12{slash}C12)") (class "Default")
      (node (ref "C29") (pin "2") (pinfunction "2_2") (pintype "passive"))
      (node (ref "R42") (pin "2") (pinfunction "2_2") (pintype "passive"))
      (node (ref "U7") (pin "4") (pinfunction "P3.0/A12/C12_4") (pintype "bidirectional"))
    )
    (net (code "52") (name "Net-(U7-P3.1{slash}A13{slash}C13)") (class "Default")
      (node (ref "C29") (pin "1") (pinfunction "1_1") (pintype "passive"))
      (node (ref "R41") (pin "2") (pinfunction "2_2") (pintype "passive"))
      (node (ref "U7") (pin "5") (pinfunction "P3.1/A13/C13_5") (pintype "bidirectional"))
    )
    (net (code "53") (name "Net-(U7-P3.2{slash}A14{slash}C14)") (class "Default")
      (node (ref "TP11") (pin "1") (pinfunction "1_1") (pintype "passive"))
      (node (ref "U7") (pin "6") (pinfunction "P3.2/A14/C14_6") (pintype "bidirectional"))
    )
    (net (code "54") (name "Net-(U7-P3.3{slash}A15{slash}C15)") (class "Default")
      (node (ref "TP12") (pin "1") (pinfunction "1_1") (pintype "passive"))
      (node (ref "U7") (pin "7") (pinfunction "P3.3/A15/C15_7") (pintype "bidirectional"))
    )
    (net (code "55") (name "Net-(U7-P4.0{slash}A8)") (class "Default")
      (node (ref "C21") (pin "2") (pinfunction "2_2") (pintype "passive"))
      (node (ref "R27") (pin "2") (pinfunction "2_2") (pintype "passive"))
      (node (ref "R29") (pin "2") (pinfunction "2_2") (pintype "passive"))
      (node (ref "U7") (pin "16") (pinfunction "P4.0/A8_16") (pintype "bidirectional"))
    )
    (net (code "56") (name "Net-(U7-P4.1{slash}A9)") (class "Default")
      (node (ref "C21") (pin "1") (pinfunction "1_1") (pintype "passive"))
      (node (ref "R28") (pin "2") (pinfunction "2_2") (pintype "passive"))
      (node (ref "R30") (pin "2") (pinfunction "2_2") (pintype "passive"))
      (node (ref "U7") (pin "17") (pinfunction "P4.1/A9_17") (pintype "bidirectional"))
    )
    (net (code "57") (name "Net-(U7-P4.2{slash}A10)") (class "Default")
      (node (ref "C22") (pin "2") (pinfunction "2_2") (pintype "passive"))
      (node (ref "R31") (pin "2") (pinfunction "2_2") (pintype "passive"))
      (node (ref "U7") (pin "18") (pinfunction "P4.2/A10_18") (pintype "bidirectional"))
    )
    (net (code "58") (name "Net-(U7-P4.3{slash}A11)") (class "Default")
      (node (ref "C22") (pin "1") (pinfunction "1_1") (pintype "passive"))
      (node (ref "R32") (pin "2") (pinfunction "2_2") (pintype "passive"))
      (node (ref "U7") (pin "19") (pinfunction "P4.3/A11_19") (pintype "bidirectional"))
    )
    (net (code "59") (name "Net-(U7-PJ.6{slash}HFXIN)") (class "Default")
      (node (ref "C48") (pin "1") (pinfunction "1_1") (pintype "passive"))
      (node (ref "U7") (pin "42") (pinfunction "PJ.6/HFXIN_42") (pintype "bidirectional"))
      (node (ref "Y2") (pin "1") (pinfunction "OSC1_1") (pintype "passive"))
    )
    (net (code "60") (name "Net-(U7-PJ.7{slash}HFXOUT)") (class "Default")
      (node (ref "C39") (pin "1") (pinfunction "1_1") (pintype "passive"))
      (node (ref "U7") (pin "43") (pinfunction "PJ.7/HFXOUT_43") (pintype "bidirectional"))
      (node (ref "Y2") (pin "2") (pinfunction "OSC2_2") (pintype "passive"))
    )
    (net (code "61") (name "unconnected-(J8-Pad1)") (class "Default")
      (node (ref "J8") (pin "1") (pinfunction "1_1") (pintype "passive+no_connect"))
    )
    (net (code "62") (name "unconnected-(J8-Pad3)") (class "Default")
      (node (ref "J8") (pin "3") (pinfunction "3_3") (pintype "passive+no_connect"))
    )
    (net (code "63") (name "unconnected-(J8-Pad13)") (class "Default")
      (node (ref "J8") (pin "13") (pinfunction "13_13") (pintype "passive+no_connect"))
    )
    (net (code "64") (name "unconnected-(J8-Pad15)") (class "Default")
      (node (ref "J8") (pin "15") (pinfunction "15_15") (pintype "passive+no_connect"))
    )
    (net (code "65") (name "unconnected-(J8-Pad19)") (class "Default")
      (node (ref "J8") (pin "19") (pinfunction "19_19") (pintype "passive+no_connect"))
    )
    (net (code "66") (name "unconnected-(J8-Pad20)") (class "Default")
      (node (ref "J8") (pin "20") (pinfunction "20_20") (pintype "passive+no_connect"))
    )
  )
)
